# func_gen.net
KiCad netlist of a schematic drawn in EAGLE
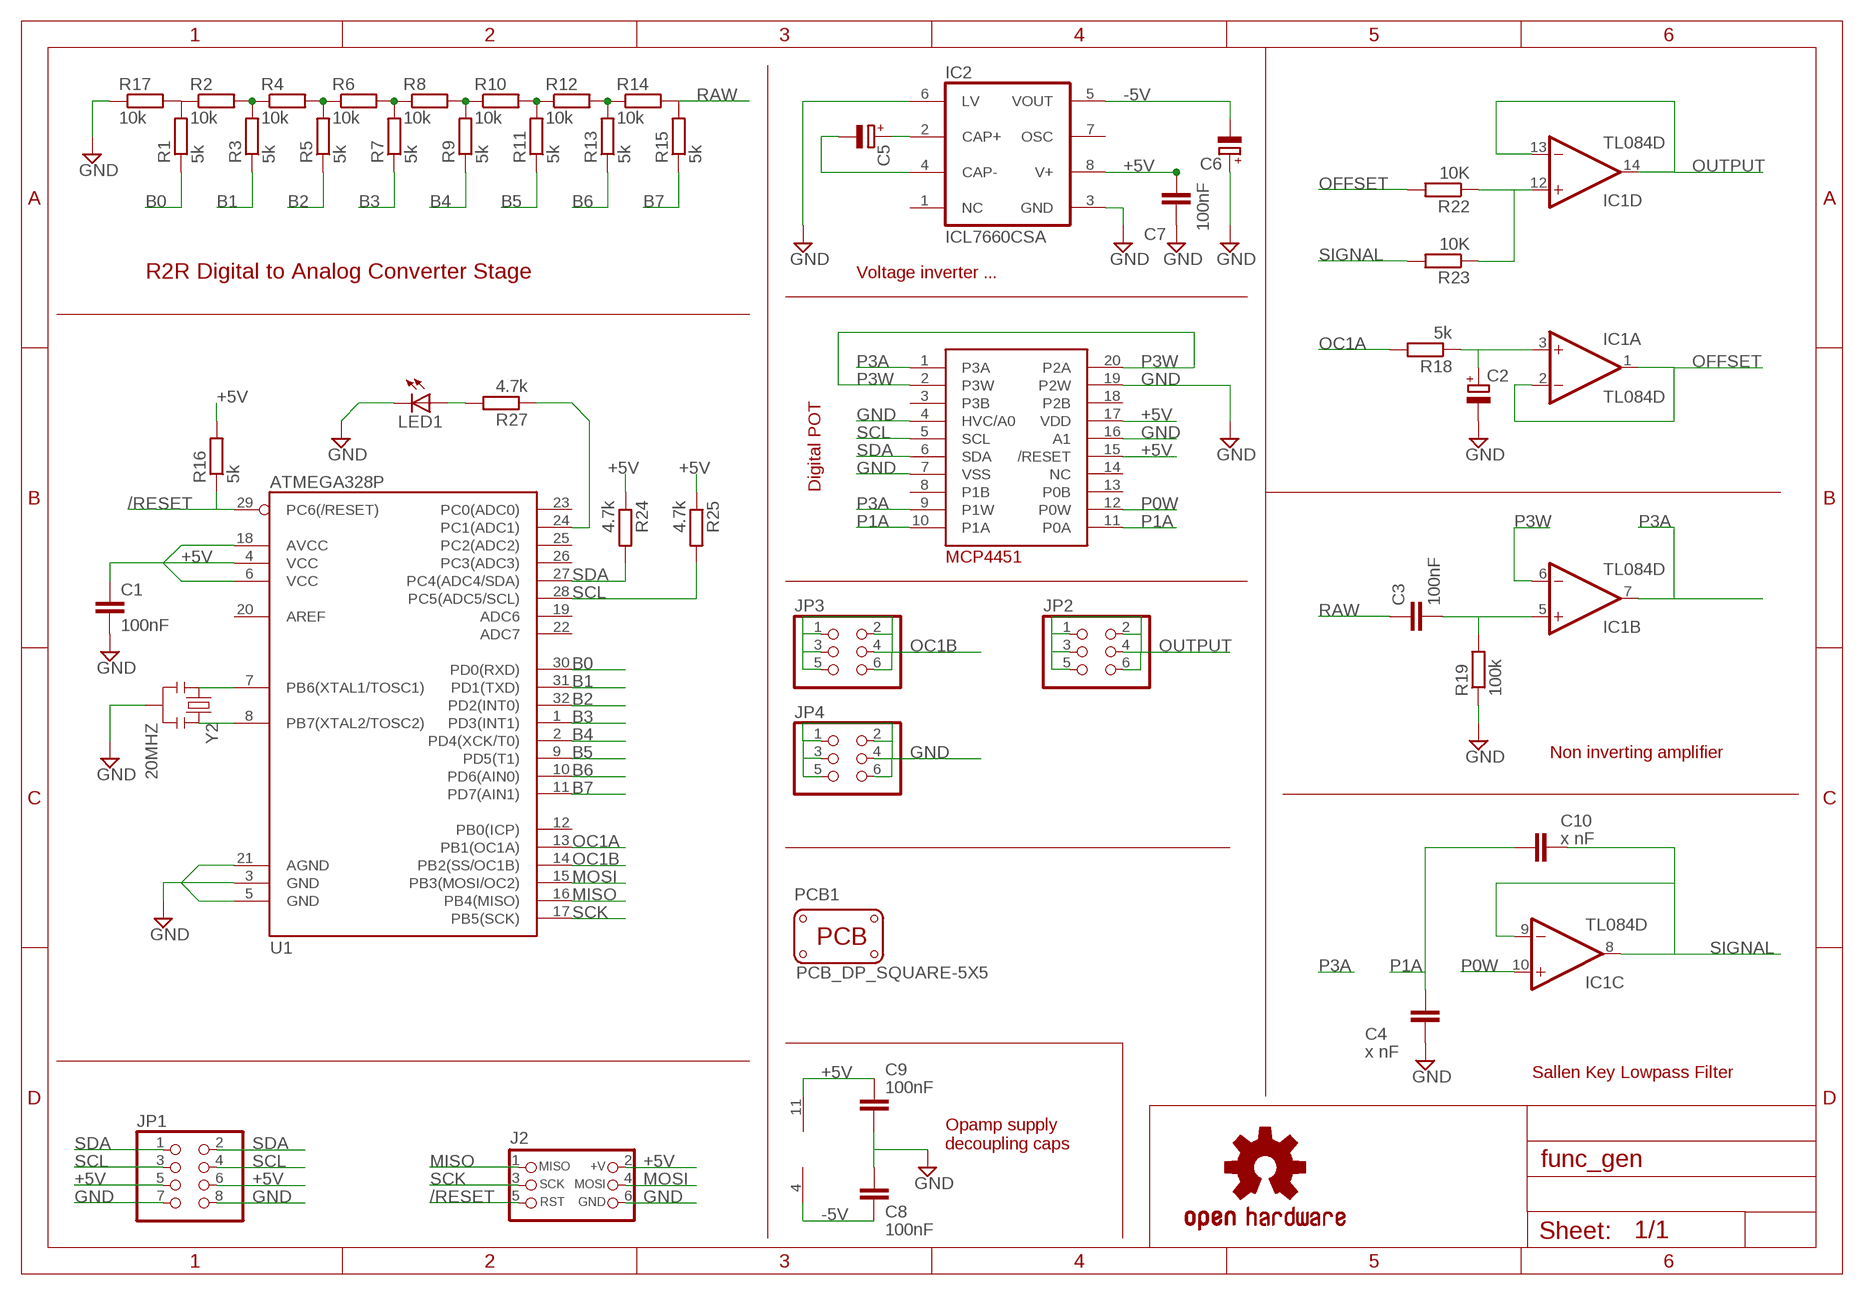
[diagram p0: schematic, sheet 1]

(export (version "E")
  (design (tool "Eeschema 10.0.6"))
  (components
    (comp (ref "C1")
      (value "100nF")
      (footprint "eagle-import:C0603")
      (libsource (lib "eagle-import") (part "C-EUC0603"))
    )
    (comp (ref "C2")
      (value "CPOL-EUE5-5")
      (footprint "eagle-import:E5-5")
      (libsource (lib "eagle-import") (part "CPOL-EUE5-5"))
    )
    (comp (ref "C3")
      (value "100nF")
      (footprint "eagle-import:C0603")
      (libsource (lib "eagle-import") (part "C-EUC0603"))
    )
    (comp (ref "C4")
      (value "x nF")
      (footprint "eagle-import:C0603")
      (libsource (lib "eagle-import") (part "C-EUC0603"))
    )
    (comp (ref "C5")
      (value "CPOL-EUE5-5")
      (footprint "eagle-import:E5-5")
      (libsource (lib "eagle-import") (part "CPOL-EUE5-5"))
    )
    (comp (ref "C6")
      (value "CPOL-EUE5-5")
      (footprint "eagle-import:E5-5")
      (libsource (lib "eagle-import") (part "CPOL-EUE5-5"))
    )
    (comp (ref "C7")
      (value "100nF")
      (footprint "eagle-import:C0603")
      (libsource (lib "eagle-import") (part "C-EUC0603"))
    )
    (comp (ref "C8")
      (value "100nF")
      (footprint "eagle-import:C0603")
      (libsource (lib "eagle-import") (part "C-EUC0603"))
    )
    (comp (ref "C9")
      (value "100nF")
      (footprint "eagle-import:C0603")
      (libsource (lib "eagle-import") (part "C-EUC0603"))
    )
    (comp (ref "C10")
      (value "x nF")
      (footprint "eagle-import:C0603")
      (libsource (lib "eagle-import") (part "C-EUC0603"))
    )
    (comp (ref "IC1")
      (value "TL084D")
      (footprint "eagle-import:SO14")
      (libsource (lib "eagle-import") (part "TL084D"))
    )
    (comp (ref "IC2")
      (value "ICL7660CSA")
      (footprint "eagle-import:SO08")
      (fields (field (name "MF") "MAXIM"))
      (libsource (lib "eagle-import") (part "ICL7660CSA"))
    )
    (comp (ref "J2")
      (value "CON_HEADER_PRG_AVR_ICSP")
      (footprint "eagle-import:HEADER_PRG_2X03")
      (libsource (lib "eagle-import") (part "CON_HEADER_PRG_AVR_ICSP"))
    )
    (comp (ref "JP1")
      (value "PINHD-2X4")
      (footprint "eagle-import:2X04")
      (libsource (lib "eagle-import") (part "PINHD-2X4"))
    )
    (comp (ref "JP2")
      (value "PINHD-2X3")
      (footprint "eagle-import:2X03")
      (libsource (lib "eagle-import") (part "PINHD-2X3"))
    )
    (comp (ref "JP3")
      (value "PINHD-2X3")
      (footprint "eagle-import:2X03")
      (libsource (lib "eagle-import") (part "PINHD-2X3"))
    )
    (comp (ref "JP4")
      (value "PINHD-2X3")
      (footprint "eagle-import:2X03")
      (libsource (lib "eagle-import") (part "PINHD-2X3"))
    )
    (comp (ref "LED1")
      (value "LED-0805")
      (footprint "eagle-import:LED-805")
      (libsource (lib "eagle-import") (part "LED-0805"))
    )
    (comp (ref "LOGO1")
      (value "OSHW-LOGOM")
      (footprint "eagle-import:OSHW-LOGO-M")
      (libsource (lib "eagle-import") (part "OSHW-LOGOM"))
    )
    (comp (ref "PCB1")
      (value "PCB_DP_SQUARE-5X5")
      (footprint "eagle-import:DP5050_V1")
      (libsource (lib "eagle-import") (part "PCB_DP_SQUARE-5X5"))
    )
    (comp (ref "R1")
      (value "5k")
      (footprint "eagle-import:R0603")
      (libsource (lib "eagle-import") (part "R-EU_R0603"))
    )
    (comp (ref "R2")
      (value "10k")
      (footprint "eagle-import:R0603")
      (libsource (lib "eagle-import") (part "R-EU_R0603"))
    )
    (comp (ref "R3")
      (value "5k")
      (footprint "eagle-import:R0603")
      (libsource (lib "eagle-import") (part "R-EU_R0603"))
    )
    (comp (ref "R4")
      (value "10k")
      (footprint "eagle-import:R0603")
      (libsource (lib "eagle-import") (part "R-EU_R0603"))
    )
    (comp (ref "R5")
      (value "5k")
      (footprint "eagle-import:R0603")
      (libsource (lib "eagle-import") (part "R-EU_R0603"))
    )
    (comp (ref "R6")
      (value "10k")
      (footprint "eagle-import:R0603")
      (libsource (lib "eagle-import") (part "R-EU_R0603"))
    )
    (comp (ref "R7")
      (value "5k")
      (footprint "eagle-import:R0603")
      (libsource (lib "eagle-import") (part "R-EU_R0603"))
    )
    (comp (ref "R8")
      (value "10k")
      (footprint "eagle-import:R0603")
      (libsource (lib "eagle-import") (part "R-EU_R0603"))
    )
    (comp (ref "R9")
      (value "5k")
      (footprint "eagle-import:R0603")
      (libsource (lib "eagle-import") (part "R-EU_R0603"))
    )
    (comp (ref "R10")
      (value "10k")
      (footprint "eagle-import:R0603")
      (libsource (lib "eagle-import") (part "R-EU_R0603"))
    )
    (comp (ref "R11")
      (value "5k")
      (footprint "eagle-import:R0603")
      (libsource (lib "eagle-import") (part "R-EU_R0603"))
    )
    (comp (ref "R12")
      (value "10k")
      (footprint "eagle-import:R0603")
      (libsource (lib "eagle-import") (part "R-EU_R0603"))
    )
    (comp (ref "R13")
      (value "5k")
      (footprint "eagle-import:R0603")
      (libsource (lib "eagle-import") (part "R-EU_R0603"))
    )
    (comp (ref "R14")
      (value "10k")
      (footprint "eagle-import:R0603")
      (libsource (lib "eagle-import") (part "R-EU_R0603"))
    )
    (comp (ref "R15")
      (value "5k")
      (footprint "eagle-import:R0603")
      (libsource (lib "eagle-import") (part "R-EU_R0603"))
    )
    (comp (ref "R16")
      (value "5k")
      (footprint "eagle-import:R0603")
      (libsource (lib "eagle-import") (part "R-EU_R0603"))
    )
    (comp (ref "R17")
      (value "10k")
      (footprint "eagle-import:R0603")
      (libsource (lib "eagle-import") (part "R-EU_R0603"))
    )
    (comp (ref "R18")
      (value "5k")
      (footprint "eagle-import:R0603")
      (libsource (lib "eagle-import") (part "R-EU_R0603"))
    )
    (comp (ref "R19")
      (value "100k")
      (footprint "eagle-import:R0603")
      (libsource (lib "eagle-import") (part "R-EU_R0603"))
    )
    (comp (ref "R22")
      (value "10K")
      (footprint "eagle-import:R0603")
      (libsource (lib "eagle-import") (part "R-EU_R0603"))
    )
    (comp (ref "R23")
      (value "10K")
      (footprint "eagle-import:R0603")
      (libsource (lib "eagle-import") (part "R-EU_R0603"))
    )
    (comp (ref "R24")
      (value "4.7k")
      (footprint "eagle-import:R0603")
      (libsource (lib "eagle-import") (part "R-EU_R0603"))
    )
    (comp (ref "R25")
      (value "4.7k")
      (footprint "eagle-import:R0603")
      (libsource (lib "eagle-import") (part "R-EU_R0603"))
    )
    (comp (ref "R27")
      (value "4.7k")
      (footprint "eagle-import:R0603")
      (libsource (lib "eagle-import") (part "R-EU_R0603"))
    )
    (comp (ref "U$1")
      (value "IHSAN_MCP4451DOGRU")
      (footprint "eagle-import:TSSOP20")
      (libsource (lib "eagle-import") (part "IHSAN_MCP4451DOGRU"))
    )
    (comp (ref "U1")
      (value "ATMEGA328P")
      (footprint "eagle-import:TQFP32-08")
      (libsource (lib "eagle-import") (part "ATMEGA328_SMT"))
    )
    (comp (ref "Y2")
      (value "20MHZ")
      (footprint "eagle-import:RESONATOR-PTH")
      (libsource (lib "eagle-import") (part "RESONATORPTH"))
    )
  )
  (nets
    (net (code "1") (name "/+5V") (class "Default")
      (node (ref "C1") (pin "1") (pinfunction "1_1") (pintype "passive"))
      (node (ref "C7") (pin "2") (pinfunction "2_2") (pintype "passive"))
      (node (ref "C9") (pin "2") (pinfunction "2_2") (pintype "passive"))
      (node (ref "IC1") (pin "11") (pinfunction "V-_11") (pintype "power_in"))
      (node (ref "IC2") (pin "8") (pinfunction "V+_8") (pintype "power_in"))
      (node (ref "J2") (pin "2") (pinfunction "+V_2") (pintype "passive"))
      (node (ref "JP1") (pin "5") (pinfunction "5_5") (pintype "passive"))
      (node (ref "JP1") (pin "6") (pinfunction "6_6") (pintype "passive"))
      (node (ref "R16") (pin "2") (pinfunction "2_2") (pintype "passive"))
      (node (ref "R24") (pin "1") (pinfunction "1_1") (pintype "passive"))
      (node (ref "R25") (pin "1") (pinfunction "1_1") (pintype "passive"))
      (node (ref "U$1") (pin "15") (pinfunction "/RESET_15") (pintype "bidirectional"))
      (node (ref "U$1") (pin "17") (pinfunction "VDD_17") (pintype "bidirectional"))
      (node (ref "U1") (pin "18") (pinfunction "AVCC_18") (pintype "bidirectional"))
      (node (ref "U1") (pin "4") (pinfunction "VCC_4") (pintype "bidirectional"))
      (node (ref "U1") (pin "6") (pinfunction "VCC_6") (pintype "bidirectional"))
    )
    (net (code "2") (name "/-5V") (class "Default")
      (node (ref "C6") (pin "-") (pinfunction "-_-") (pintype "passive"))
      (node (ref "C8") (pin "1") (pinfunction "1_1") (pintype "passive"))
      (node (ref "IC1") (pin "4") (pinfunction "V+_4") (pintype "power_in"))
      (node (ref "IC2") (pin "5") (pinfunction "VOUT_5") (pintype "output"))
    )
    (net (code "3") (name "/B0") (class "Default")
      (node (ref "R1") (pin "1") (pinfunction "1_1") (pintype "passive"))
      (node (ref "U1") (pin "30") (pinfunction "PD0(RXD)_30") (pintype "bidirectional"))
    )
    (net (code "4") (name "/B1") (class "Default")
      (node (ref "R3") (pin "1") (pinfunction "1_1") (pintype "passive"))
      (node (ref "U1") (pin "31") (pinfunction "PD1(TXD)_31") (pintype "bidirectional"))
    )
    (net (code "5") (name "/B2") (class "Default")
      (node (ref "R5") (pin "1") (pinfunction "1_1") (pintype "passive"))
      (node (ref "U1") (pin "32") (pinfunction "PD2(INT0)_32") (pintype "bidirectional"))
    )
    (net (code "6") (name "/B3") (class "Default")
      (node (ref "R7") (pin "1") (pinfunction "1_1") (pintype "passive"))
      (node (ref "U1") (pin "1") (pinfunction "PD3(INT1)_1") (pintype "bidirectional"))
    )
    (net (code "7") (name "/B4") (class "Default")
      (node (ref "R9") (pin "1") (pinfunction "1_1") (pintype "passive"))
      (node (ref "U1") (pin "2") (pinfunction "PD4(XCK/T0)_2") (pintype "bidirectional"))
    )
    (net (code "8") (name "/B5") (class "Default")
      (node (ref "R11") (pin "1") (pinfunction "1_1") (pintype "passive"))
      (node (ref "U1") (pin "9") (pinfunction "PD5(T1)_9") (pintype "bidirectional"))
    )
    (net (code "9") (name "/B6") (class "Default")
      (node (ref "R13") (pin "1") (pinfunction "1_1") (pintype "passive"))
      (node (ref "U1") (pin "10") (pinfunction "PD6(AIN0)_10") (pintype "bidirectional"))
    )
    (net (code "10") (name "/B7") (class "Default")
      (node (ref "R15") (pin "1") (pinfunction "1_1") (pintype "passive"))
      (node (ref "U1") (pin "11") (pinfunction "PD7(AIN1)_11") (pintype "bidirectional"))
    )
    (net (code "11") (name "/MISO") (class "Default")
      (node (ref "J2") (pin "1") (pinfunction "MISO_1") (pintype "passive"))
      (node (ref "U1") (pin "16") (pinfunction "PB4(MISO)_16") (pintype "bidirectional"))
    )
    (net (code "12") (name "/MOSI") (class "Default")
      (node (ref "J2") (pin "4") (pinfunction "MOSI_4") (pintype "passive"))
      (node (ref "U1") (pin "15") (pinfunction "PB3(MOSI/OC2)_15") (pintype "bidirectional"))
    )
    (net (code "13") (name "/OC1A") (class "Default")
      (node (ref "R18") (pin "2") (pinfunction "2_2") (pintype "passive"))
      (node (ref "U1") (pin "13") (pinfunction "PB1(OC1A)_13") (pintype "bidirectional"))
    )
    (net (code "14") (name "/OC1B") (class "Default")
      (node (ref "JP3") (pin "1") (pinfunction "1_1") (pintype "passive"))
      (node (ref "JP3") (pin "2") (pinfunction "2_2") (pintype "passive"))
      (node (ref "JP3") (pin "3") (pinfunction "3_3") (pintype "passive"))
      (node (ref "JP3") (pin "4") (pinfunction "4_4") (pintype "passive"))
      (node (ref "JP3") (pin "5") (pinfunction "5_5") (pintype "passive"))
      (node (ref "JP3") (pin "6") (pinfunction "6_6") (pintype "passive"))
      (node (ref "U1") (pin "14") (pinfunction "PB2(SS/OC1B)_14") (pintype "bidirectional"))
    )
    (net (code "15") (name "/OFFSET") (class "Default")
      (node (ref "IC1") (pin "1") (pinfunction "OUT_1") (pintype "output"))
      (node (ref "IC1") (pin "2") (pinfunction "-IN_2") (pintype "input"))
      (node (ref "R22") (pin "2") (pinfunction "2_2") (pintype "passive"))
    )
    (net (code "16") (name "/OUTPUT") (class "Default")
      (node (ref "IC1") (pin "13") (pinfunction "-IN_13") (pintype "input"))
      (node (ref "IC1") (pin "14") (pinfunction "OUT_14") (pintype "output"))
      (node (ref "JP2") (pin "1") (pinfunction "1_1") (pintype "passive"))
      (node (ref "JP2") (pin "2") (pinfunction "2_2") (pintype "passive"))
      (node (ref "JP2") (pin "3") (pinfunction "3_3") (pintype "passive"))
      (node (ref "JP2") (pin "4") (pinfunction "4_4") (pintype "passive"))
      (node (ref "JP2") (pin "5") (pinfunction "5_5") (pintype "passive"))
      (node (ref "JP2") (pin "6") (pinfunction "6_6") (pintype "passive"))
    )
    (net (code "17") (name "/P0W") (class "Default")
      (node (ref "IC1") (pin "10") (pinfunction "+IN_10") (pintype "input"))
      (node (ref "U$1") (pin "12") (pinfunction "P0W_12") (pintype "bidirectional"))
    )
    (net (code "18") (name "/P1A") (class "Default")
      (node (ref "C10") (pin "1") (pinfunction "1_1") (pintype "passive"))
      (node (ref "C4") (pin "2") (pinfunction "2_2") (pintype "passive"))
      (node (ref "U$1") (pin "10") (pinfunction "P1A_10") (pintype "bidirectional"))
      (node (ref "U$1") (pin "11") (pinfunction "P0A_11") (pintype "bidirectional"))
    )
    (net (code "19") (name "/P3A") (class "Default")
      (node (ref "IC1") (pin "7") (pinfunction "OUT_7") (pintype "output"))
      (node (ref "U$1") (pin "1") (pinfunction "P3A_1") (pintype "bidirectional"))
      (node (ref "U$1") (pin "9") (pinfunction "P1W_9") (pintype "bidirectional"))
    )
    (net (code "20") (name "/P3W") (class "Default")
      (node (ref "IC1") (pin "6") (pinfunction "-IN_6") (pintype "input"))
      (node (ref "U$1") (pin "2") (pinfunction "P3W_2") (pintype "bidirectional"))
      (node (ref "U$1") (pin "20") (pinfunction "P2A_20") (pintype "bidirectional"))
    )
    (net (code "21") (name "/RAW") (class "Default")
      (node (ref "C3") (pin "1") (pinfunction "1_1") (pintype "passive"))
      (node (ref "R14") (pin "2") (pinfunction "2_2") (pintype "passive"))
      (node (ref "R15") (pin "2") (pinfunction "2_2") (pintype "passive"))
    )
    (net (code "22") (name "/SCK") (class "Default")
      (node (ref "J2") (pin "3") (pinfunction "SCK_3") (pintype "passive"))
      (node (ref "U1") (pin "17") (pinfunction "PB5(SCK)_17") (pintype "bidirectional"))
    )
    (net (code "23") (name "/SCL") (class "Default")
      (node (ref "JP1") (pin "3") (pinfunction "3_3") (pintype "passive"))
      (node (ref "JP1") (pin "4") (pinfunction "4_4") (pintype "passive"))
      (node (ref "R25") (pin "2") (pinfunction "2_2") (pintype "passive"))
      (node (ref "U$1") (pin "5") (pinfunction "SCL_5") (pintype "bidirectional"))
      (node (ref "U1") (pin "28") (pinfunction "PC5(ADC5/SCL)_28") (pintype "bidirectional"))
    )
    (net (code "24") (name "/SDA") (class "Default")
      (node (ref "JP1") (pin "1") (pinfunction "1_1") (pintype "passive"))
      (node (ref "JP1") (pin "2") (pinfunction "2_2") (pintype "passive"))
      (node (ref "R24") (pin "2") (pinfunction "2_2") (pintype "passive"))
      (node (ref "U$1") (pin "6") (pinfunction "SDA_6") (pintype "bidirectional"))
      (node (ref "U1") (pin "27") (pinfunction "PC4(ADC4/SDA)_27") (pintype "bidirectional"))
    )
    (net (code "25") (name "/SIGNAL") (class "Default")
      (node (ref "C10") (pin "2") (pinfunction "2_2") (pintype "passive"))
      (node (ref "IC1") (pin "8") (pinfunction "OUT_8") (pintype "output"))
      (node (ref "IC1") (pin "9") (pinfunction "-IN_9") (pintype "input"))
      (node (ref "R23") (pin "2") (pinfunction "2_2") (pintype "passive"))
    )
    (net (code "26") (name "/{slash}RESET") (class "Default")
      (node (ref "J2") (pin "5") (pinfunction "RST_5") (pintype "passive"))
      (node (ref "R16") (pin "1") (pinfunction "1_1") (pintype "passive"))
      (node (ref "U1") (pin "29") (pinfunction "PC6(/RESET)_29") (pintype "bidirectional"))
    )
    (net (code "27") (name "GND") (class "Default")
      (node (ref "C1") (pin "2") (pinfunction "2_2") (pintype "passive"))
      (node (ref "C2") (pin "-") (pinfunction "-_-") (pintype "passive"))
      (node (ref "C4") (pin "1") (pinfunction "1_1") (pintype "passive"))
      (node (ref "C6") (pin "+") (pinfunction "+_+") (pintype "passive"))
      (node (ref "C7") (pin "1") (pinfunction "1_1") (pintype "passive"))
      (node (ref "C8") (pin "2") (pinfunction "2_2") (pintype "passive"))
      (node (ref "C9") (pin "1") (pinfunction "1_1") (pintype "passive"))
      (node (ref "IC2") (pin "3") (pinfunction "GND_3") (pintype "power_in"))
      (node (ref "IC2") (pin "6") (pinfunction "LV_6") (pintype "passive"))
      (node (ref "J2") (pin "6") (pinfunction "GND_6") (pintype "passive"))
      (node (ref "JP1") (pin "7") (pinfunction "7_7") (pintype "passive"))
      (node (ref "JP1") (pin "8") (pinfunction "8_8") (pintype "passive"))
      (node (ref "JP4") (pin "1") (pinfunction "1_1") (pintype "passive"))
      (node (ref "JP4") (pin "2") (pinfunction "2_2") (pintype "passive"))
      (node (ref "JP4") (pin "3") (pinfunction "3_3") (pintype "passive"))
      (node (ref "JP4") (pin "4") (pinfunction "4_4") (pintype "passive"))
      (node (ref "JP4") (pin "5") (pinfunction "5_5") (pintype "passive"))
      (node (ref "JP4") (pin "6") (pinfunction "6_6") (pintype "passive"))
      (node (ref "LED1") (pin "C") (pinfunction "C_C") (pintype "passive"))
      (node (ref "R17") (pin "1") (pinfunction "1_1") (pintype "passive"))
      (node (ref "R19") (pin "1") (pinfunction "1_1") (pintype "passive"))
      (node (ref "U$1") (pin "16") (pinfunction "A1_16") (pintype "bidirectional"))
      (node (ref "U$1") (pin "19") (pinfunction "P2W_19") (pintype "bidirectional"))
      (node (ref "U$1") (pin "4") (pinfunction "HVC/A0_4") (pintype "bidirectional"))
      (node (ref "U$1") (pin "7") (pinfunction "VSS_7") (pintype "bidirectional"))
      (node (ref "U1") (pin "21") (pinfunction "AGND_21") (pintype "bidirectional"))
      (node (ref "U1") (pin "3") (pinfunction "GND_3") (pintype "bidirectional"))
      (node (ref "U1") (pin "5") (pinfunction "GND_5") (pintype "bidirectional"))
      (node (ref "Y2") (pin "2") (pinfunction "2_2") (pintype "passive"))
    )
    (net (code "28") (name "Net-(IC1A-+IN)") (class "Default")
      (node (ref "C2") (pin "+") (pinfunction "+_+") (pintype "passive"))
      (node (ref "IC1") (pin "3") (pinfunction "+IN_3") (pintype "input"))
      (node (ref "R18") (pin "1") (pinfunction "1_1") (pintype "passive"))
    )
    (net (code "29") (name "Net-(IC1B-+IN)") (class "Default")
      (node (ref "C3") (pin "2") (pinfunction "2_2") (pintype "passive"))
      (node (ref "IC1") (pin "5") (pinfunction "+IN_5") (pintype "input"))
      (node (ref "R19") (pin "2") (pinfunction "2_2") (pintype "passive"))
    )
    (net (code "30") (name "Net-(IC1D-+IN)") (class "Default")
      (node (ref "IC1") (pin "12") (pinfunction "+IN_12") (pintype "input"))
      (node (ref "R22") (pin "1") (pinfunction "1_1") (pintype "passive"))
      (node (ref "R23") (pin "1") (pinfunction "1_1") (pintype "passive"))
    )
    (net (code "31") (name "Net-(IC2-CAP+)") (class "Default")
      (node (ref "C5") (pin "+") (pinfunction "+_+") (pintype "passive"))
      (node (ref "IC2") (pin "2") (pinfunction "CAP+_2") (pintype "passive"))
    )
    (net (code "32") (name "Net-(IC2-CAP-)") (class "Default")
      (node (ref "C5") (pin "-") (pinfunction "-_-") (pintype "passive"))
      (node (ref "IC2") (pin "4") (pinfunction "CAP-_4") (pintype "passive"))
    )
    (net (code "33") (name "Net-(LED1-PadA)") (class "Default")
      (node (ref "LED1") (pin "A") (pinfunction "A_A") (pintype "passive"))
      (node (ref "R27") (pin "2") (pinfunction "2_2") (pintype "passive"))
    )
    (net (code "34") (name "Net-(R1-Pad2)") (class "Default")
      (node (ref "R1") (pin "2") (pinfunction "2_2") (pintype "passive"))
      (node (ref "R17") (pin "2") (pinfunction "2_2") (pintype "passive"))
      (node (ref "R2") (pin "1") (pinfunction "1_1") (pintype "passive"))
    )
    (net (code "35") (name "Net-(R2-Pad2)") (class "Default")
      (node (ref "R2") (pin "2") (pinfunction "2_2") (pintype "passive"))
      (node (ref "R3") (pin "2") (pinfunction "2_2") (pintype "passive"))
      (node (ref "R4") (pin "1") (pinfunction "1_1") (pintype "passive"))
    )
    (net (code "36") (name "Net-(R4-Pad2)") (class "Default")
      (node (ref "R4") (pin "2") (pinfunction "2_2") (pintype "passive"))
      (node (ref "R5") (pin "2") (pinfunction "2_2") (pintype "passive"))
      (node (ref "R6") (pin "1") (pinfunction "1_1") (pintype "passive"))
    )
    (net (code "37") (name "Net-(R6-Pad2)") (class "Default")
      (node (ref "R6") (pin "2") (pinfunction "2_2") (pintype "passive"))
      (node (ref "R7") (pin "2") (pinfunction "2_2") (pintype "passive"))
      (node (ref "R8") (pin "1") (pinfunction "1_1") (pintype "passive"))
    )
    (net (code "38") (name "Net-(R10-Pad1)") (class "Default")
      (node (ref "R10") (pin "1") (pinfunction "1_1") (pintype "passive"))
      (node (ref "R8") (pin "2") (pinfunction "2_2") (pintype "passive"))
      (node (ref "R9") (pin "2") (pinfunction "2_2") (pintype "passive"))
    )
    (net (code "39") (name "Net-(R10-Pad2)") (class "Default")
      (node (ref "R10") (pin "2") (pinfunction "2_2") (pintype "passive"))
      (node (ref "R11") (pin "2") (pinfunction "2_2") (pintype "passive"))
      (node (ref "R12") (pin "1") (pinfunction "1_1") (pintype "passive"))
    )
    (net (code "40") (name "Net-(R12-Pad2)") (class "Default")
      (node (ref "R12") (pin "2") (pinfunction "2_2") (pintype "passive"))
      (node (ref "R13") (pin "2") (pinfunction "2_2") (pintype "passive"))
      (node (ref "R14") (pin "1") (pinfunction "1_1") (pintype "passive"))
    )
    (net (code "41") (name "Net-(U1-PB6(XTAL1{slash}TOSC1))") (class "Default")
      (node (ref "U1") (pin "7") (pinfunction "PB6(XTAL1/TOSC1)_7") (pintype "bidirectional"))
      (node (ref "Y2") (pin "1") (pinfunction "1_1") (pintype "passive"))
    )
    (net (code "42") (name "Net-(U1-PB7(XTAL2{slash}TOSC2))") (class "Default")
      (node (ref "U1") (pin "8") (pinfunction "PB7(XTAL2/TOSC2)_8") (pintype "bidirectional"))
      (node (ref "Y2") (pin "3") (pinfunction "3_3") (pintype "passive"))
    )
    (net (code "43") (name "Net-(U1-PC1(ADC1))") (class "Default")
      (node (ref "R27") (pin "1") (pinfunction "1_1") (pintype "passive"))
      (node (ref "U1") (pin "24") (pinfunction "PC1(ADC1)_24") (pintype "bidirectional"))
    )
    (net (code "44") (name "unconnected-(IC2-NC-Pad1)") (class "Default")
      (node (ref "IC2") (pin "1") (pinfunction "NC_1") (pintype "no_connect"))
    )
    (net (code "45") (name "unconnected-(IC2-OSC-Pad7)") (class "Default")
      (node (ref "IC2") (pin "7") (pinfunction "OSC_7") (pintype "output"))
    )
    (net (code "46") (name "unconnected-(U$1-NC-Pad14)") (class "Default")
      (node (ref "U$1") (pin "14") (pinfunction "NC_14") (pintype "bidirectional"))
    )
    (net (code "47") (name "unconnected-(U$1-P0B-Pad13)") (class "Default")
      (node (ref "U$1") (pin "13") (pinfunction "P0B_13") (pintype "bidirectional"))
    )
    (net (code "48") (name "unconnected-(U$1-P1B-Pad8)") (class "Default")
      (node (ref "U$1") (pin "8") (pinfunction "P1B_8") (pintype "bidirectional"))
    )
    (net (code "49") (name "unconnected-(U$1-P2B-Pad18)") (class "Default")
      (node (ref "U$1") (pin "18") (pinfunction "P2B_18") (pintype "bidirectional"))
    )
    (net (code "50") (name "unconnected-(U$1-P3B-Pad3)") (class "Default")
      (node (ref "U$1") (pin "3") (pinfunction "P3B_3") (pintype "bidirectional"))
    )
    (net (code "51") (name "unconnected-(U1-ADC6-Pad19)") (class "Default")
      (node (ref "U1") (pin "19") (pinfunction "ADC6_19") (pintype "bidirectional"))
    )
    (net (code "52") (name "unconnected-(U1-ADC7-Pad22)") (class "Default")
      (node (ref "U1") (pin "22") (pinfunction "ADC7_22") (pintype "bidirectional"))
    )
    (net (code "53") (name "unconnected-(U1-AREF-Pad20)") (class "Default")
      (node (ref "U1") (pin "20") (pinfunction "AREF_20") (pintype "bidirectional"))
    )
    (net (code "54") (name "unconnected-(U1-PB0(ICP)-Pad12)") (class "Default")
      (node (ref "U1") (pin "12") (pinfunction "PB0(ICP)_12") (pintype "bidirectional"))
    )
    (net (code "55") (name "unconnected-(U1-PC0(ADC0)-Pad23)") (class "Default")
      (node (ref "U1") (pin "23") (pinfunction "PC0(ADC0)_23") (pintype "bidirectional"))
    )
    (net (code "56") (name "unconnected-(U1-PC2(ADC2)-Pad25)") (class "Default")
      (node (ref "U1") (pin "25") (pinfunction "PC2(ADC2)_25") (pintype "bidirectional"))
    )
    (net (code "57") (name "unconnected-(U1-PC3(ADC3)-Pad26)") (class "Default")
      (node (ref "U1") (pin "26") (pinfunction "PC3(ADC3)_26") (pintype "bidirectional"))
    )
  )
)
